# USBSmartSwitch.net
KiCad netlist of a schematic drawn in EAGLE
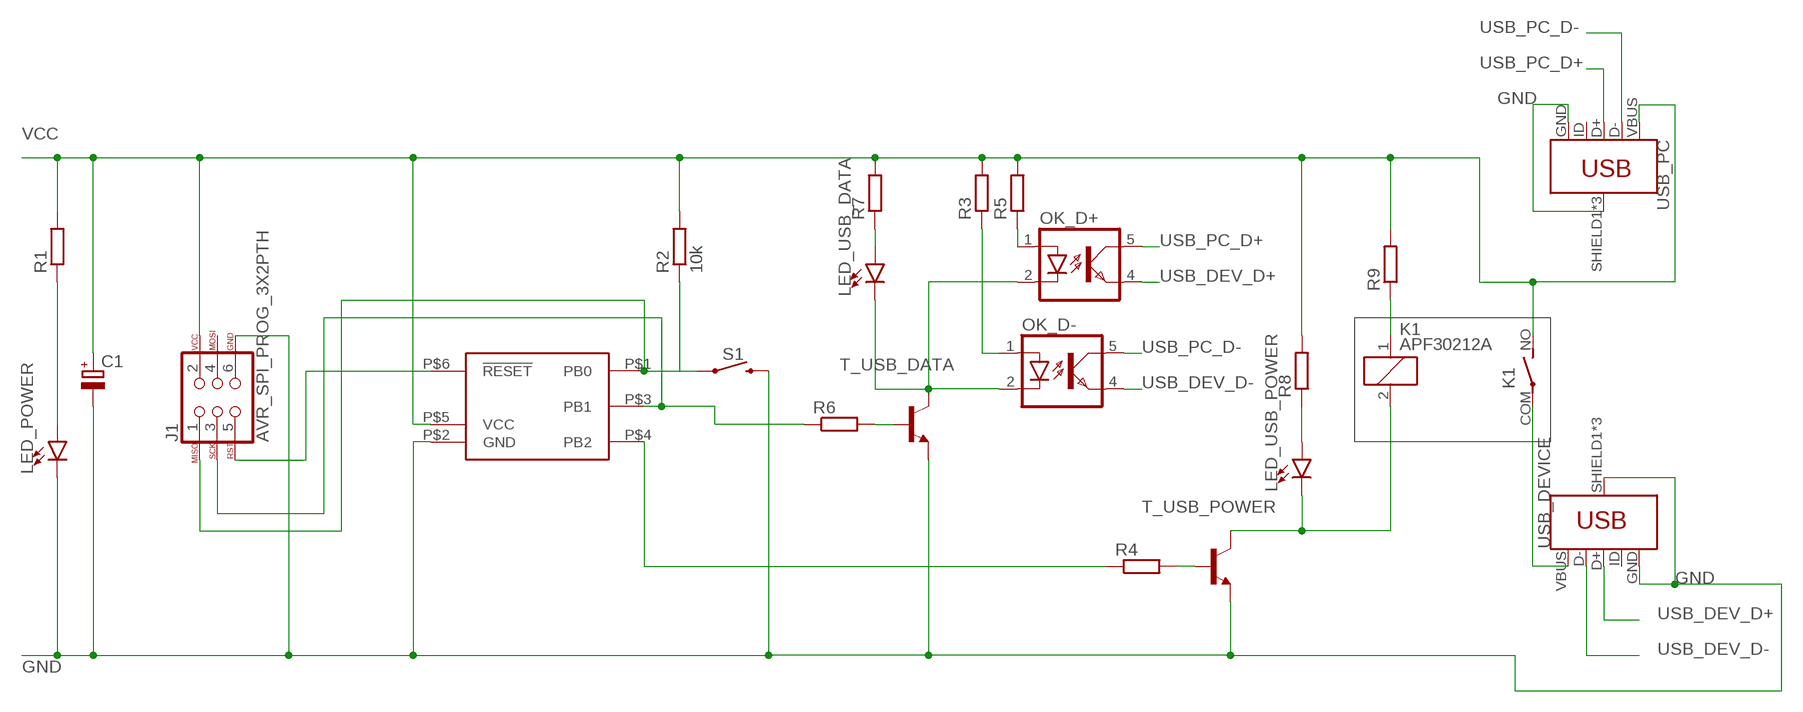
[diagram p0: schematic, sheet 1]

(export (version "E")
  (design (tool "Eeschema 10.0.6"))
  (components
    (comp (ref "C1")
      (value "CPOL-EUE2-5")
      (footprint "eagle-import:E2-5")
      (libsource (lib "eagle-import") (part "CPOL-EUE2-5"))
    )
    (comp (ref "J1")
      (value "AVR_SPI_PROG_3X2PTH")
      (footprint "eagle-import:2X3")
      (libsource (lib "eagle-import") (part "AVR_SPI_PROG_3X2PTH"))
    )
    (comp (ref "K1")
      (value "APF30212A")
      (footprint "eagle-import:APF30212A")
      (libsource (lib "eagle-import") (part "APF30212A"))
    )
    (comp (ref "LED_POWER")
      (value "LED3MM")
      (footprint "eagle-import:LED_3MM")
      (libsource (lib "eagle-import") (part "LED3MM"))
    )
    (comp (ref "LED_USB_DATA")
      (value "LED3MM")
      (footprint "eagle-import:LED_3MM")
      (libsource (lib "eagle-import") (part "LED3MM"))
    )
    (comp (ref "LED_USB_POWER")
      (value "LED3MM")
      (footprint "eagle-import:LED_3MM")
      (libsource (lib "eagle-import") (part "LED3MM"))
    )
    (comp (ref "OK_D+")
      (value "CNF17GF")
      (footprint "eagle-import:DIL06B")
      (libsource (lib "eagle-import") (part "CNF17GF"))
    )
    (comp (ref "OK_D-")
      (value "CNF17GF")
      (footprint "eagle-import:DIL06B")
      (libsource (lib "eagle-import") (part "CNF17GF"))
    )
    (comp (ref "R1")
      (value "R-EU_0204/7")
      (footprint "eagle-import:0204_7")
      (libsource (lib "eagle-import") (part "R-EU_0204/7"))
    )
    (comp (ref "R2")
      (value "10k")
      (footprint "eagle-import:0204_7")
      (libsource (lib "eagle-import") (part "R-EU_0204/7"))
    )
    (comp (ref "R3")
      (value "R-EU_0204/7")
      (footprint "eagle-import:0204_7")
      (libsource (lib "eagle-import") (part "R-EU_0204/7"))
    )
    (comp (ref "R4")
      (value "R-EU_0204/7")
      (footprint "eagle-import:0204_7")
      (libsource (lib "eagle-import") (part "R-EU_0204/7"))
    )
    (comp (ref "R5")
      (value "R-EU_0204/7")
      (footprint "eagle-import:0204_7")
      (libsource (lib "eagle-import") (part "R-EU_0204/7"))
    )
    (comp (ref "R6")
      (value "R-EU_0204/7")
      (footprint "eagle-import:0204_7")
      (libsource (lib "eagle-import") (part "R-EU_0204/7"))
    )
    (comp (ref "R7")
      (value "R-EU_0204/7")
      (footprint "eagle-import:0204_7")
      (libsource (lib "eagle-import") (part "R-EU_0204/7"))
    )
    (comp (ref "R8")
      (value "R-EU_0204/7")
      (footprint "eagle-import:0204_7")
      (libsource (lib "eagle-import") (part "R-EU_0204/7"))
    )
    (comp (ref "R9")
      (value "R-EU_0204/7")
      (footprint "eagle-import:0204_7")
      (libsource (lib "eagle-import") (part "R-EU_0204/7"))
    )
    (comp (ref "S1")
      (value "MOMENTARY-SWITCH-SPST-PTH-6.0MM")
      (footprint "eagle-import:TACTILE_SWITCH_PTH_6.0MM")
      (libsource (lib "eagle-import") (part "MOMENTARY-SWITCH-SPST-PTH-6.0MM"))
    )
    (comp (ref "T_USB_DATA")
      (value "-NPN-TO92")
      (footprint "eagle-import:TO92")
      (libsource (lib "eagle-import") (part "-NPN-TO92"))
    )
    (comp (ref "T_USB_POWER")
      (value "-NPN-TO92")
      (footprint "eagle-import:TO92")
      (libsource (lib "eagle-import") (part "-NPN-TO92"))
    )
    (comp (ref "U$1")
      (value "ATTINY10")
      (footprint "eagle-import:SOT23")
      (libsource (lib "eagle-import") (part "ATTINY10"))
    )
    (comp (ref "USB_DEVICE")
      (value "USB_MICRO-BREDUCED_PASTE")
      (footprint "eagle-import:USB-B-MICRO-SMD_RED_PASTE")
      (libsource (lib "eagle-import") (part "USB_MICRO-BREDUCED_PASTE"))
    )
    (comp (ref "USB_PC")
      (value "USB_MICRO-BREDUCED_PASTE")
      (footprint "eagle-import:USB-B-MICRO-SMD_RED_PASTE")
      (libsource (lib "eagle-import") (part "USB_MICRO-BREDUCED_PASTE"))
    )
  )
  (nets
    (net (code "1") (name "/GND") (class "Default")
      (node (ref "C1") (pin "-") (pinfunction "-_-") (pintype "passive"))
      (node (ref "J1") (pin "6") (pinfunction "6_6") (pintype "passive"))
      (node (ref "LED_POWER") (pin "K") (pinfunction "C_K") (pintype "passive"))
      (node (ref "S1") (pin "3") (pinfunction "2_3") (pintype "passive"))
      (node (ref "T_USB_DATA") (pin "1") (pinfunction "E_1") (pintype "passive"))
      (node (ref "T_USB_POWER") (pin "1") (pinfunction "E_1") (pintype "passive"))
      (node (ref "U$1") (pin "P$2") (pinfunction "GND_P$2") (pintype "bidirectional"))
      (node (ref "USB_DEVICE") (pin "GND") (pinfunction "GND_GND") (pintype "power_in"))
      (node (ref "USB_DEVICE") (pin "SHIELD1") (pinfunction "SHIELD_SHIELD1") (pintype "bidirectional"))
      (node (ref "USB_DEVICE") (pin "SHIELD2") (pinfunction "SHIELD_SHIELD2") (pintype "bidirectional"))
      (node (ref "USB_DEVICE") (pin "SHIELD3") (pinfunction "SHIELD_SHIELD3") (pintype "bidirectional"))
      (node (ref "USB_PC") (pin "GND") (pinfunction "GND_GND") (pintype "power_in"))
      (node (ref "USB_PC") (pin "SHIELD1") (pinfunction "SHIELD_SHIELD1") (pintype "bidirectional"))
      (node (ref "USB_PC") (pin "SHIELD2") (pinfunction "SHIELD_SHIELD2") (pintype "bidirectional"))
      (node (ref "USB_PC") (pin "SHIELD3") (pinfunction "SHIELD_SHIELD3") (pintype "bidirectional"))
    )
    (net (code "2") (name "/USB_DEV_D+") (class "Default")
      (node (ref "OK_D+") (pin "4") (pinfunction "EMIT_4") (pintype "passive"))
      (node (ref "USB_DEVICE") (pin "D+") (pinfunction "D+_D+") (pintype "bidirectional"))
    )
    (net (code "3") (name "/USB_DEV_D-") (class "Default")
      (node (ref "OK_D-") (pin "4") (pinfunction "EMIT_4") (pintype "passive"))
      (node (ref "USB_DEVICE") (pin "D-") (pinfunction "D-_D-") (pintype "bidirectional"))
    )
    (net (code "4") (name "/USB_PC_D+") (class "Default")
      (node (ref "OK_D+") (pin "5") (pinfunction "COL_5") (pintype "passive"))
      (node (ref "USB_PC") (pin "D+") (pinfunction "D+_D+") (pintype "bidirectional"))
    )
    (net (code "5") (name "/USB_PC_D-") (class "Default")
      (node (ref "OK_D-") (pin "5") (pinfunction "COL_5") (pintype "passive"))
      (node (ref "USB_PC") (pin "D-") (pinfunction "D-_D-") (pintype "bidirectional"))
    )
    (net (code "6") (name "/VCC") (class "Default")
      (node (ref "C1") (pin "+") (pinfunction "+_+") (pintype "passive"))
      (node (ref "J1") (pin "2") (pinfunction "2_2") (pintype "passive"))
      (node (ref "K1") (pin "NO") (pinfunction "S_NO") (pintype "passive"))
      (node (ref "R1") (pin "2") (pinfunction "2_2") (pintype "passive"))
      (node (ref "R2") (pin "2") (pinfunction "2_2") (pintype "passive"))
      (node (ref "R3") (pin "2") (pinfunction "2_2") (pintype "passive"))
      (node (ref "R5") (pin "2") (pinfunction "2_2") (pintype "passive"))
      (node (ref "R7") (pin "2") (pinfunction "2_2") (pintype "passive"))
      (node (ref "R8") (pin "2") (pinfunction "2_2") (pintype "passive"))
      (node (ref "R9") (pin "2") (pinfunction "2_2") (pintype "passive"))
      (node (ref "U$1") (pin "P$5") (pinfunction "VCC_P$5") (pintype "bidirectional"))
      (node (ref "USB_PC") (pin "VBUS") (pinfunction "VBUS_VBUS") (pintype "power_in"))
    )
    (net (code "7") (name "Net-(K1-Pad1)") (class "Default")
      (node (ref "K1") (pin "1") (pinfunction "1_1") (pintype "passive"))
      (node (ref "R9") (pin "1") (pinfunction "1_1") (pintype "passive"))
    )
    (net (code "8") (name "Net-(K1B-P)") (class "Default")
      (node (ref "K1") (pin "COM") (pinfunction "P_COM") (pintype "passive"))
      (node (ref "USB_DEVICE") (pin "VBUS") (pinfunction "VBUS_VBUS") (pintype "power_in"))
    )
    (net (code "9") (name "Net-(LED_POWER-PadA)") (class "Default")
      (node (ref "LED_POWER") (pin "A") (pinfunction "A_A") (pintype "passive"))
      (node (ref "R1") (pin "1") (pinfunction "1_1") (pintype "passive"))
    )
    (net (code "10") (name "Net-(LED_USB_DATA-C)") (class "Default")
      (node (ref "LED_USB_DATA") (pin "K") (pinfunction "C_K") (pintype "passive"))
      (node (ref "OK_D+") (pin "2") (pinfunction "C_2") (pintype "passive"))
      (node (ref "OK_D-") (pin "2") (pinfunction "C_2") (pintype "passive"))
      (node (ref "T_USB_DATA") (pin "3") (pinfunction "C_3") (pintype "passive"))
    )
    (net (code "11") (name "Net-(LED_USB_DATA-PadA)") (class "Default")
      (node (ref "LED_USB_DATA") (pin "A") (pinfunction "A_A") (pintype "passive"))
      (node (ref "R7") (pin "1") (pinfunction "1_1") (pintype "passive"))
    )
    (net (code "12") (name "Net-(LED_USB_POWER-C)") (class "Default")
      (node (ref "K1") (pin "2") (pinfunction "2_2") (pintype "passive"))
      (node (ref "LED_USB_POWER") (pin "K") (pinfunction "C_K") (pintype "passive"))
      (node (ref "T_USB_POWER") (pin "3") (pinfunction "C_3") (pintype "passive"))
    )
    (net (code "13") (name "Net-(LED_USB_POWER-PadA)") (class "Default")
      (node (ref "LED_USB_POWER") (pin "A") (pinfunction "A_A") (pintype "passive"))
      (node (ref "R8") (pin "1") (pinfunction "1_1") (pintype "passive"))
    )
    (net (code "14") (name "Net-(OK_D+-A)") (class "Default")
      (node (ref "OK_D+") (pin "1") (pinfunction "A_1") (pintype "passive"))
      (node (ref "R5") (pin "1") (pinfunction "1_1") (pintype "passive"))
    )
    (net (code "15") (name "Net-(OK_D--A)") (class "Default")
      (node (ref "OK_D-") (pin "1") (pinfunction "A_1") (pintype "passive"))
      (node (ref "R3") (pin "1") (pinfunction "1_1") (pintype "passive"))
    )
    (net (code "16") (name "Net-(T_USB_DATA-B)") (class "Default")
      (node (ref "R6") (pin "2") (pinfunction "2_2") (pintype "passive"))
      (node (ref "T_USB_DATA") (pin "2") (pinfunction "B_2") (pintype "passive"))
    )
    (net (code "17") (name "Net-(T_USB_POWER-B)") (class "Default")
      (node (ref "R4") (pin "2") (pinfunction "2_2") (pintype "passive"))
      (node (ref "T_USB_POWER") (pin "2") (pinfunction "B_2") (pintype "passive"))
    )
    (net (code "18") (name "Net-(U$1-PB0)") (class "Default")
      (node (ref "J1") (pin "1") (pinfunction "1_1") (pintype "passive"))
      (node (ref "R2") (pin "1") (pinfunction "1_1") (pintype "passive"))
      (node (ref "S1") (pin "1") (pinfunction "1_1") (pintype "passive"))
      (node (ref "U$1") (pin "P$1") (pinfunction "PB0_P$1") (pintype "bidirectional"))
    )
    (net (code "19") (name "Net-(U$1-PB1)") (class "Default")
      (node (ref "J1") (pin "3") (pinfunction "3_3") (pintype "passive"))
      (node (ref "R6") (pin "1") (pinfunction "1_1") (pintype "passive"))
      (node (ref "U$1") (pin "P$3") (pinfunction "PB1_P$3") (pintype "bidirectional"))
    )
    (net (code "20") (name "Net-(U$1-PB2)") (class "Default")
      (node (ref "R4") (pin "1") (pinfunction "1_1") (pintype "passive"))
      (node (ref "U$1") (pin "P$4") (pinfunction "PB2_P$4") (pintype "bidirectional"))
    )
    (net (code "21") (name "Net-(U$1-~{RESET})") (class "Default")
      (node (ref "J1") (pin "5") (pinfunction "5_5") (pintype "passive"))
      (node (ref "U$1") (pin "P$6") (pinfunction "~{RESET}_P$6") (pintype "bidirectional"))
    )
    (net (code "22") (name "unconnected-(J1-Pad4)") (class "Default")
      (node (ref "J1") (pin "4") (pinfunction "4_4") (pintype "passive"))
    )
    (net (code "23") (name "unconnected-(USB_DEVICE-PadID)") (class "Default")
      (node (ref "USB_DEVICE") (pin "ID") (pinfunction "ID_ID") (pintype "bidirectional"))
    )
    (net (code "24") (name "unconnected-(USB_PC-PadID)") (class "Default")
      (node (ref "USB_PC") (pin "ID") (pinfunction "ID_ID") (pintype "bidirectional"))
    )
  )
)
